# 8-Kanal-DIN-BASE_V2.net
KiCad netlist of a schematic drawn in EAGLE
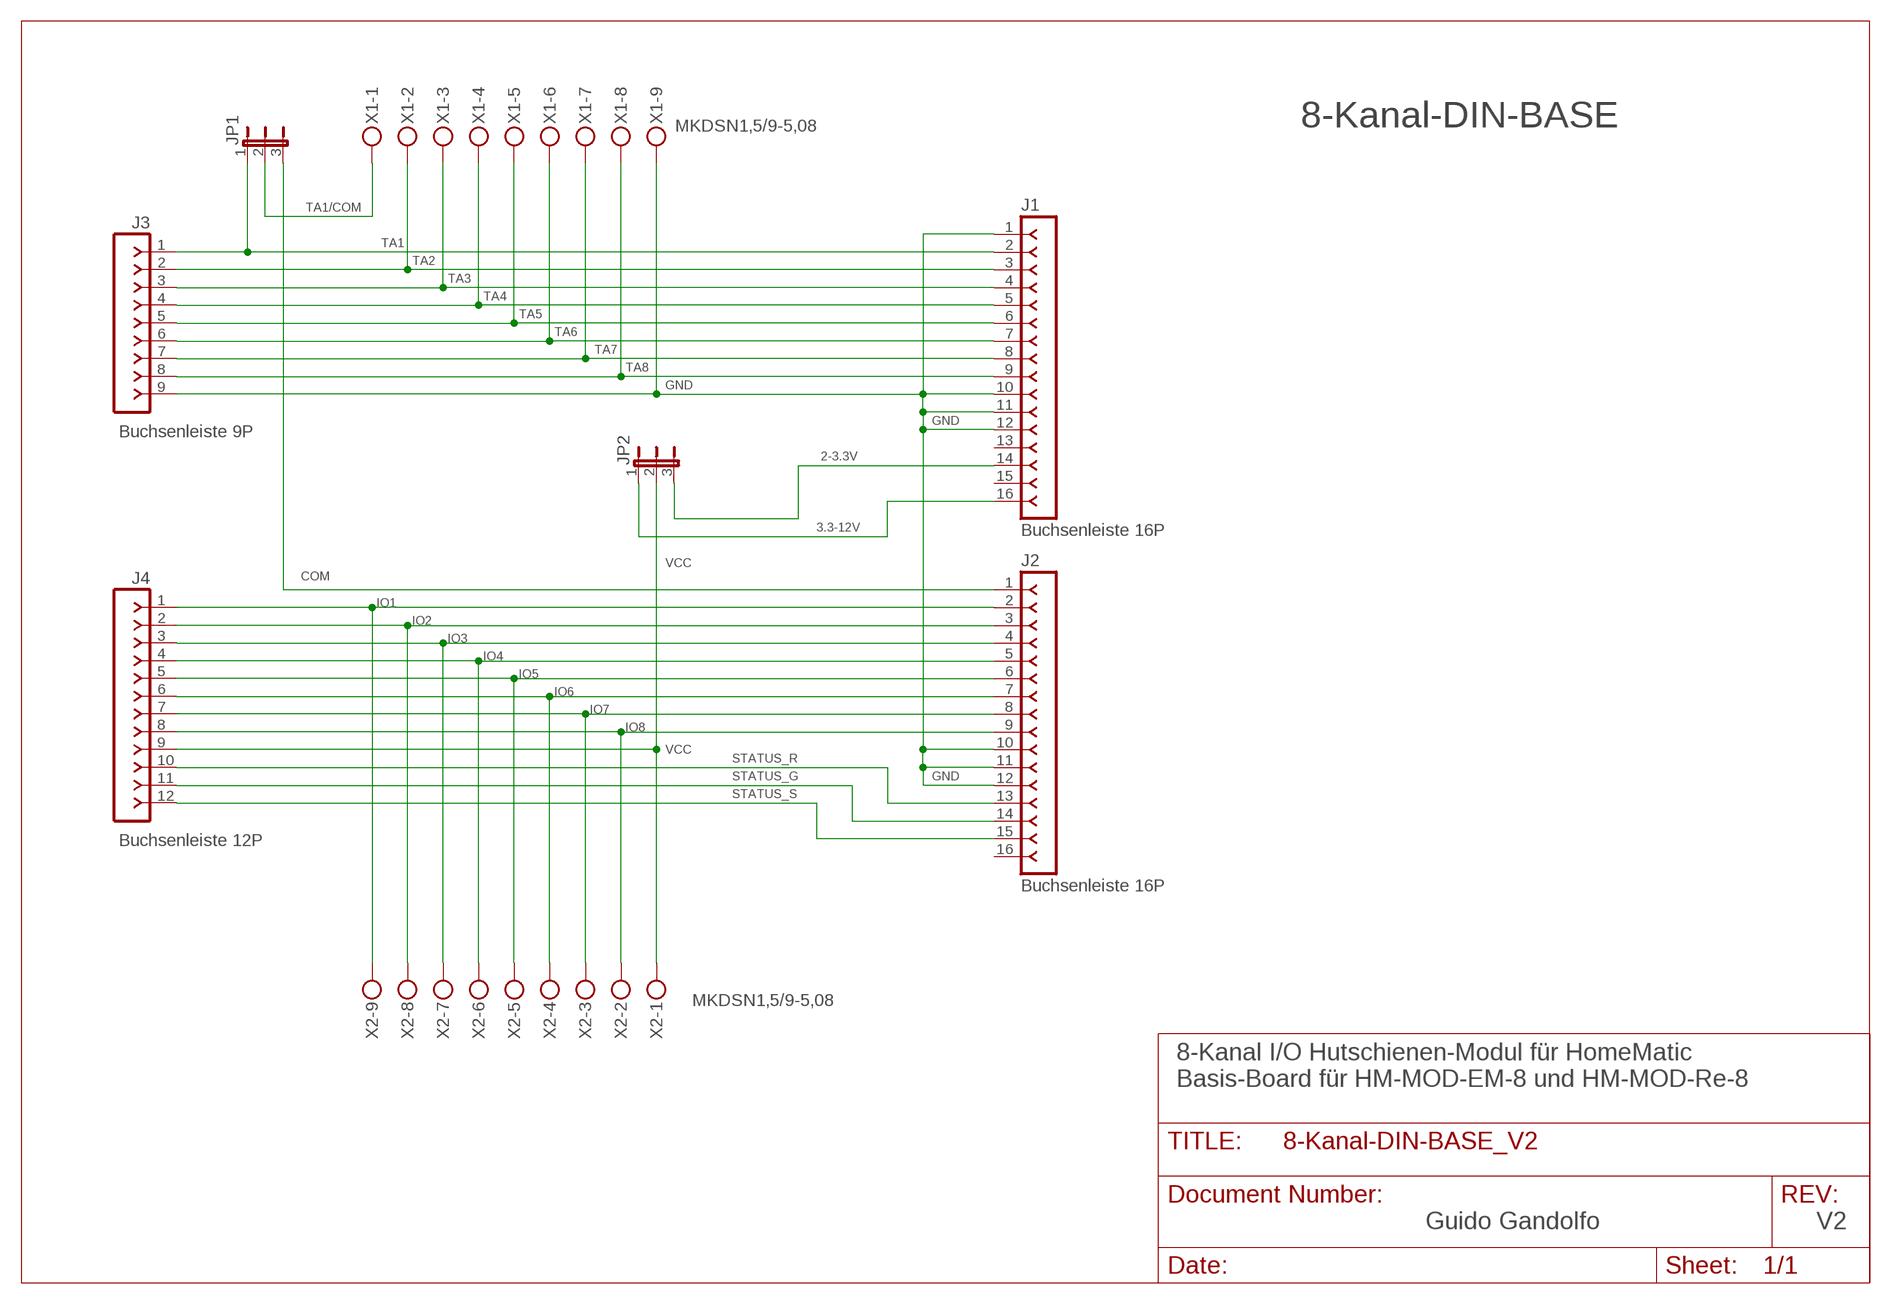
[diagram p0: schematic, sheet 1]

(export (version "E")
  (design (tool "Eeschema 10.0.6"))
  (components
    (comp (ref "J1")
      (value "Buchsenleiste 16P")
      (footprint "eagle-import:SIP-100-16-40Y")
      (libsource (lib "eagle-import") (part "F-1X16-SIP-100-40Y"))
    )
    (comp (ref "J2")
      (value "Buchsenleiste 16P")
      (footprint "eagle-import:SIP-100-16-40Y")
      (libsource (lib "eagle-import") (part "F-1X16-SIP-100-40Y"))
    )
    (comp (ref "J3")
      (value "Buchsenleiste 9P")
      (footprint "eagle-import:SIP-100-09-40Y")
      (libsource (lib "eagle-import") (part "F-1X09-SIP-100-40Y"))
    )
    (comp (ref "J4")
      (value "Buchsenleiste 12P")
      (footprint "eagle-import:SIP-100-12-40Y")
      (libsource (lib "eagle-import") (part "F-1X12-SIP-100-40Y"))
    )
    (comp (ref "JP1")
      (value "JP2E")
      (footprint "eagle-import:JP2")
      (libsource (lib "eagle-import") (part "JP2E"))
    )
    (comp (ref "JP2")
      (value "JP2E")
      (footprint "eagle-import:JP2")
      (libsource (lib "eagle-import") (part "JP2E"))
    )
    (comp (ref "X1")
      (value "MKDSN1,5/9-5,08")
      (footprint "eagle-import:MKDSN1,5_9-5,08")
      (fields (field (name "MPN") "SMKDSN1,5/9-5,08"))
      (libsource (lib "eagle-import") (part "MKDSN1,5/9-5,08"))
    )
    (comp (ref "X2")
      (value "MKDSN1,5/9-5,08")
      (footprint "eagle-import:MKDSN1,5_9-5,08")
      (fields (field (name "MPN") "SMKDSN1,5/9-5,08"))
      (libsource (lib "eagle-import") (part "MKDSN1,5/9-5,08"))
    )
  )
  (nets
    (net (code "1") (name "/2-3.3V") (class "Default")
      (node (ref "J1") (pin "14") (pinfunction "14_14") (pintype "passive"))
      (node (ref "JP2") (pin "3") (pinfunction "3_3") (pintype "passive"))
    )
    (net (code "2") (name "/3.3-12V") (class "Default")
      (node (ref "J1") (pin "16") (pinfunction "16_16") (pintype "passive"))
      (node (ref "JP2") (pin "1") (pinfunction "1_1") (pintype "passive"))
    )
    (net (code "3") (name "/COM") (class "Default")
      (node (ref "J2") (pin "1") (pinfunction "1_1") (pintype "passive"))
      (node (ref "JP1") (pin "3") (pinfunction "3_3") (pintype "passive"))
    )
    (net (code "4") (name "/GND") (class "Default")
      (node (ref "J1") (pin "1") (pinfunction "1_1") (pintype "passive"))
      (node (ref "J1") (pin "10") (pinfunction "10_10") (pintype "passive"))
      (node (ref "J1") (pin "11") (pinfunction "11_11") (pintype "passive"))
      (node (ref "J1") (pin "12") (pinfunction "12_12") (pintype "passive"))
      (node (ref "J2") (pin "10") (pinfunction "10_10") (pintype "passive"))
      (node (ref "J2") (pin "11") (pinfunction "11_11") (pintype "passive"))
      (node (ref "J2") (pin "12") (pinfunction "12_12") (pintype "passive"))
      (node (ref "J3") (pin "9") (pinfunction "9_9") (pintype "passive"))
      (node (ref "X1") (pin "9") (pinfunction "KL_9") (pintype "passive"))
    )
    (net (code "5") (name "/IO1") (class "Default")
      (node (ref "J2") (pin "2") (pinfunction "2_2") (pintype "passive"))
      (node (ref "J4") (pin "1") (pinfunction "1_1") (pintype "passive"))
      (node (ref "X2") (pin "9") (pinfunction "KL_9") (pintype "passive"))
    )
    (net (code "6") (name "/IO2") (class "Default")
      (node (ref "J2") (pin "3") (pinfunction "3_3") (pintype "passive"))
      (node (ref "J4") (pin "2") (pinfunction "2_2") (pintype "passive"))
      (node (ref "X2") (pin "8") (pinfunction "KL_8") (pintype "passive"))
    )
    (net (code "7") (name "/IO3") (class "Default")
      (node (ref "J2") (pin "4") (pinfunction "4_4") (pintype "passive"))
      (node (ref "J4") (pin "3") (pinfunction "3_3") (pintype "passive"))
      (node (ref "X2") (pin "7") (pinfunction "KL_7") (pintype "passive"))
    )
    (net (code "8") (name "/IO4") (class "Default")
      (node (ref "J2") (pin "5") (pinfunction "5_5") (pintype "passive"))
      (node (ref "J4") (pin "4") (pinfunction "4_4") (pintype "passive"))
      (node (ref "X2") (pin "6") (pinfunction "KL_6") (pintype "passive"))
    )
    (net (code "9") (name "/IO5") (class "Default")
      (node (ref "J2") (pin "6") (pinfunction "6_6") (pintype "passive"))
      (node (ref "J4") (pin "5") (pinfunction "5_5") (pintype "passive"))
      (node (ref "X2") (pin "5") (pinfunction "KL_5") (pintype "passive"))
    )
    (net (code "10") (name "/IO6") (class "Default")
      (node (ref "J2") (pin "7") (pinfunction "7_7") (pintype "passive"))
      (node (ref "J4") (pin "6") (pinfunction "6_6") (pintype "passive"))
      (node (ref "X2") (pin "4") (pinfunction "KL_4") (pintype "passive"))
    )
    (net (code "11") (name "/IO7") (class "Default")
      (node (ref "J2") (pin "8") (pinfunction "8_8") (pintype "passive"))
      (node (ref "J4") (pin "7") (pinfunction "7_7") (pintype "passive"))
      (node (ref "X2") (pin "3") (pinfunction "KL_3") (pintype "passive"))
    )
    (net (code "12") (name "/IO8") (class "Default")
      (node (ref "J2") (pin "9") (pinfunction "9_9") (pintype "passive"))
      (node (ref "J4") (pin "8") (pinfunction "8_8") (pintype "passive"))
      (node (ref "X2") (pin "2") (pinfunction "KL_2") (pintype "passive"))
    )
    (net (code "13") (name "/STATUS_G") (class "Default")
      (node (ref "J2") (pin "14") (pinfunction "14_14") (pintype "passive"))
      (node (ref "J4") (pin "11") (pinfunction "11_11") (pintype "passive"))
    )
    (net (code "14") (name "/STATUS_R") (class "Default")
      (node (ref "J2") (pin "13") (pinfunction "13_13") (pintype "passive"))
      (node (ref "J4") (pin "10") (pinfunction "10_10") (pintype "passive"))
    )
    (net (code "15") (name "/STATUS_S") (class "Default")
      (node (ref "J2") (pin "15") (pinfunction "15_15") (pintype "passive"))
      (node (ref "J4") (pin "12") (pinfunction "12_12") (pintype "passive"))
    )
    (net (code "16") (name "/TA1") (class "Default")
      (node (ref "J1") (pin "2") (pinfunction "2_2") (pintype "passive"))
      (node (ref "J3") (pin "1") (pinfunction "1_1") (pintype "passive"))
      (node (ref "JP1") (pin "1") (pinfunction "1_1") (pintype "passive"))
    )
    (net (code "17") (name "/TA1{slash}COM") (class "Default")
      (node (ref "JP1") (pin "2") (pinfunction "2_2") (pintype "passive"))
      (node (ref "X1") (pin "1") (pinfunction "KL_1") (pintype "passive"))
    )
    (net (code "18") (name "/TA2") (class "Default")
      (node (ref "J1") (pin "3") (pinfunction "3_3") (pintype "passive"))
      (node (ref "J3") (pin "2") (pinfunction "2_2") (pintype "passive"))
      (node (ref "X1") (pin "2") (pinfunction "KL_2") (pintype "passive"))
    )
    (net (code "19") (name "/TA3") (class "Default")
      (node (ref "J1") (pin "4") (pinfunction "4_4") (pintype "passive"))
      (node (ref "J3") (pin "3") (pinfunction "3_3") (pintype "passive"))
      (node (ref "X1") (pin "3") (pinfunction "KL_3") (pintype "passive"))
    )
    (net (code "20") (name "/TA4") (class "Default")
      (node (ref "J1") (pin "5") (pinfunction "5_5") (pintype "passive"))
      (node (ref "J3") (pin "4") (pinfunction "4_4") (pintype "passive"))
      (node (ref "X1") (pin "4") (pinfunction "KL_4") (pintype "passive"))
    )
    (net (code "21") (name "/TA5") (class "Default")
      (node (ref "J1") (pin "6") (pinfunction "6_6") (pintype "passive"))
      (node (ref "J3") (pin "5") (pinfunction "5_5") (pintype "passive"))
      (node (ref "X1") (pin "5") (pinfunction "KL_5") (pintype "passive"))
    )
    (net (code "22") (name "/TA6") (class "Default")
      (node (ref "J1") (pin "7") (pinfunction "7_7") (pintype "passive"))
      (node (ref "J3") (pin "6") (pinfunction "6_6") (pintype "passive"))
      (node (ref "X1") (pin "6") (pinfunction "KL_6") (pintype "passive"))
    )
    (net (code "23") (name "/TA7") (class "Default")
      (node (ref "J1") (pin "8") (pinfunction "8_8") (pintype "passive"))
      (node (ref "J3") (pin "7") (pinfunction "7_7") (pintype "passive"))
      (node (ref "X1") (pin "7") (pinfunction "KL_7") (pintype "passive"))
    )
    (net (code "24") (name "/TA8") (class "Default")
      (node (ref "J1") (pin "9") (pinfunction "9_9") (pintype "passive"))
      (node (ref "J3") (pin "8") (pinfunction "8_8") (pintype "passive"))
      (node (ref "X1") (pin "8") (pinfunction "KL_8") (pintype "passive"))
    )
    (net (code "25") (name "/VCC") (class "Default")
      (node (ref "J4") (pin "9") (pinfunction "9_9") (pintype "passive"))
      (node (ref "JP2") (pin "2") (pinfunction "2_2") (pintype "passive"))
      (node (ref "X2") (pin "1") (pinfunction "KL_1") (pintype "passive"))
    )
    (net (code "26") (name "unconnected-(J1-Pad13)") (class "Default")
      (node (ref "J1") (pin "13") (pinfunction "13_13") (pintype "passive"))
    )
    (net (code "27") (name "unconnected-(J1-Pad15)") (class "Default")
      (node (ref "J1") (pin "15") (pinfunction "15_15") (pintype "passive"))
    )
    (net (code "28") (name "unconnected-(J2-Pad16)") (class "Default")
      (node (ref "J2") (pin "16") (pinfunction "16_16") (pintype "passive"))
    )
  )
)
